# MOSFETS.net
KiCad netlist of a schematic drawn in Altium Designer
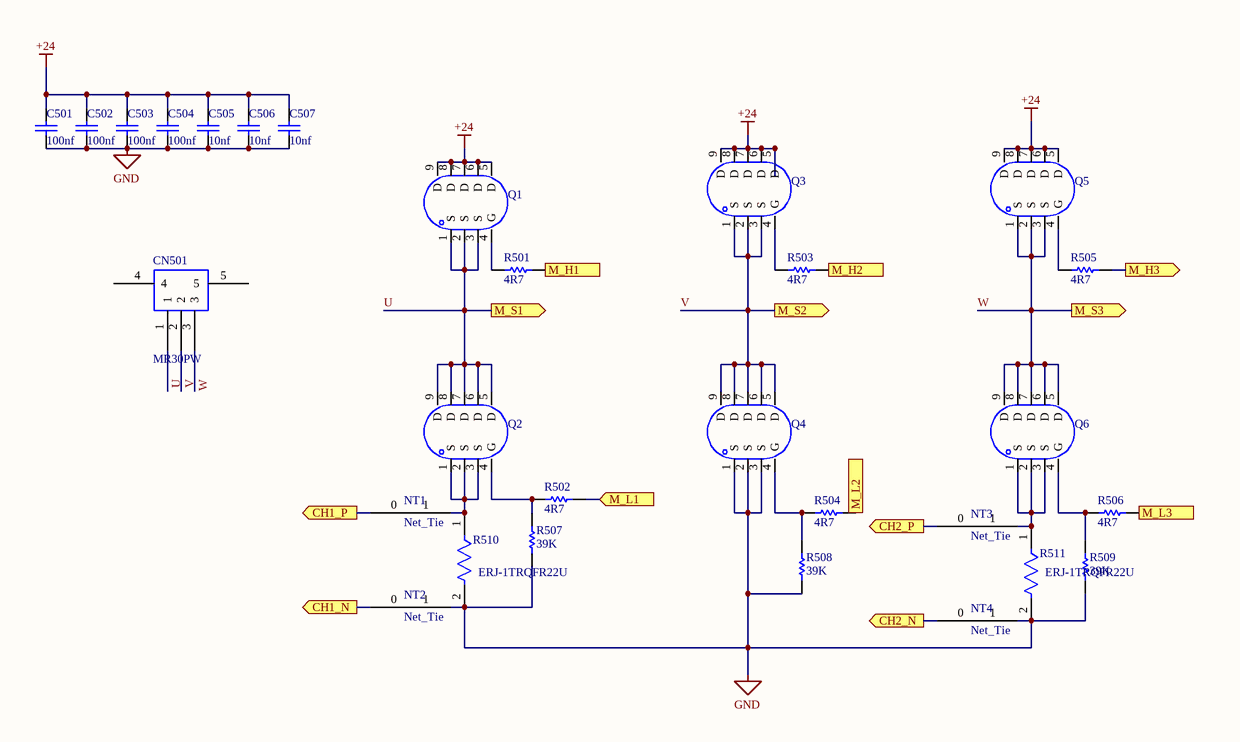
[diagram p0: MOSFETS.SchDoc]

(export (version "E")
  (design (tool "Eeschema 10.0.6"))
  (components
    (comp (ref "C501")
      (value "100nf")
      (footprint "AVX-1206-2_L")
      (description "Chip Capacitor, 1 nF, +/- 10%, -55 to 125 degC, 1206 (3216 Metric), RoHS, Tape and Reel")
      (fields (field (name "TOLERANCE") "10%") (field (name "PARTNUMBER") "1206GC102KAT1A"))
      (libsource (lib "Altium Content Vault") (part "CAP-NP-2"))
    )
    (comp (ref "C502")
      (value "100nf")
      (footprint "AVX-1206-2_L")
      (description "Chip Capacitor, 1 nF, +/- 10%, -55 to 125 degC, 1206 (3216 Metric), RoHS, Tape and Reel")
      (fields (field (name "TOLERANCE") "10%") (field (name "PARTNUMBER") "1206GC102KAT1A"))
      (libsource (lib "Altium Content Vault") (part "CAP-NP-2"))
    )
    (comp (ref "C503")
      (value "100nf")
      (footprint "AVX-1206-2_L")
      (description "Chip Capacitor, 1 nF, +/- 10%, -55 to 125 degC, 1206 (3216 Metric), RoHS, Tape and Reel")
      (fields (field (name "TOLERANCE") "10%") (field (name "PARTNUMBER") "1206GC102KAT1A"))
      (libsource (lib "Altium Content Vault") (part "CAP-NP-2"))
    )
    (comp (ref "C504")
      (value "100nf")
      (footprint "AVX-1206-2_L")
      (description "Chip Capacitor, 1 nF, +/- 10%, -55 to 125 degC, 1206 (3216 Metric), RoHS, Tape and Reel")
      (fields (field (name "TOLERANCE") "10%") (field (name "PARTNUMBER") "1206GC102KAT1A"))
      (libsource (lib "Altium Content Vault") (part "CAP-NP-2"))
    )
    (comp (ref "C505")
      (value "10nf")
      (footprint "AVX-1206-2_L")
      (description "Chip Capacitor, 1 nF, +/- 10%, -55 to 125 degC, 1206 (3216 Metric), RoHS, Tape and Reel")
      (fields (field (name "TOLERANCE") "10%") (field (name "PARTNUMBER") "1206GC102KAT1A"))
      (libsource (lib "Altium Content Vault") (part "CAP-NP-2"))
    )
    (comp (ref "C506")
      (value "10nf")
      (footprint "AVX-1206-2_L")
      (description "Chip Capacitor, 1 nF, +/- 10%, -55 to 125 degC, 1206 (3216 Metric), RoHS, Tape and Reel")
      (fields (field (name "TOLERANCE") "10%") (field (name "PARTNUMBER") "1206GC102KAT1A"))
      (libsource (lib "Altium Content Vault") (part "CAP-NP-2"))
    )
    (comp (ref "C507")
      (value "10nf")
      (footprint "AVX-1206-2_L")
      (description "Chip Capacitor, 1 nF, +/- 10%, -55 to 125 degC, 1206 (3216 Metric), RoHS, Tape and Reel")
      (fields (field (name "TOLERANCE") "10%") (field (name "PARTNUMBER") "1206GC102KAT1A"))
      (libsource (lib "Altium Content Vault") (part "CAP-NP-2"))
    )
    (comp (ref "CN501") (value "MR30PW") (footprint "MR30") (libsource (lib "MR30PW") (part "Component_1")))
    (comp (ref "NT1") (value "Net_Tie") (footprint "NT") (libsource (lib "NT") (part "Net_Tie")))
    (comp (ref "NT2") (value "Net_Tie") (footprint "NT") (libsource (lib "NT") (part "Net_Tie")))
    (comp (ref "NT3") (value "Net_Tie") (footprint "NT") (libsource (lib "NT") (part "Net_Tie")))
    (comp (ref "NT4") (value "Net_Tie") (footprint "NT") (libsource (lib "NT") (part "Net_Tie")))
    (comp (ref "Q1")
      (value "TPH1R403NL")
      (footprint "DSOP-8_L5.0-W5.0-P1.27-EP-TL")
      (fields (field (name "MANUFACTURER") "TOSHIBA(东芝)"))
      (libsource (lib "TPH1R403NL") (part "TPH1R403NL"))
    )
    (comp (ref "Q2")
      (value "TPH1R403NL")
      (footprint "DSOP-8_L5.0-W5.0-P1.27-EP-TL")
      (fields (field (name "MANUFACTURER") "TOSHIBA(东芝)"))
      (libsource (lib "TPH1R403NL") (part "TPH1R403NL"))
    )
    (comp (ref "Q3")
      (value "TPH1R403NL")
      (footprint "DSOP-8_L5.0-W5.0-P1.27-EP-TL")
      (fields (field (name "MANUFACTURER") "TOSHIBA(东芝)"))
      (libsource (lib "TPH1R403NL") (part "TPH1R403NL"))
    )
    (comp (ref "Q4")
      (value "TPH1R403NL")
      (footprint "DSOP-8_L5.0-W5.0-P1.27-EP-TL")
      (fields (field (name "MANUFACTURER") "TOSHIBA(东芝)"))
      (libsource (lib "TPH1R403NL") (part "TPH1R403NL"))
    )
    (comp (ref "Q5")
      (value "TPH1R403NL")
      (footprint "DSOP-8_L5.0-W5.0-P1.27-EP-TL")
      (fields (field (name "MANUFACTURER") "TOSHIBA(东芝)"))
      (libsource (lib "TPH1R403NL") (part "TPH1R403NL"))
    )
    (comp (ref "Q6")
      (value "TPH1R403NL")
      (footprint "DSOP-8_L5.0-W5.0-P1.27-EP-TL")
      (fields (field (name "MANUFACTURER") "TOSHIBA(东芝)"))
      (libsource (lib "TPH1R403NL") (part "TPH1R403NL"))
    )
    (comp (ref "R501")
      (value "4R7")
      (footprint "RESC1608X55X25ML10T15")
      (description "Chip Resistor, 0 Ohm, +/- 5%, 0.1 W, -55 to 155 degC, 0603 (1608 Metric), RoHS, Tape and Reel")
      (fields (field (name "TOLERANCE") "5%") (field (name "MANUFACTURER") "Yageo"))
      (libsource (lib "Altium Content Vault") (part "RES-2"))
    )
    (comp (ref "R502")
      (value "4R7")
      (footprint "RESC1608X55X25ML10T15")
      (description "Chip Resistor, 0 Ohm, +/- 5%, 0.1 W, -55 to 155 degC, 0603 (1608 Metric), RoHS, Tape and Reel")
      (fields (field (name "TOLERANCE") "5%") (field (name "MANUFACTURER") "Yageo"))
      (libsource (lib "Altium Content Vault") (part "RES-2"))
    )
    (comp (ref "R503")
      (value "4R7")
      (footprint "RESC1608X55X25ML10T15")
      (description "Chip Resistor, 0 Ohm, +/- 5%, 0.1 W, -55 to 155 degC, 0603 (1608 Metric), RoHS, Tape and Reel")
      (fields (field (name "TOLERANCE") "5%") (field (name "MANUFACTURER") "Yageo"))
      (libsource (lib "Altium Content Vault") (part "RES-2"))
    )
    (comp (ref "R504")
      (value "4R7")
      (footprint "RESC1608X55X25ML10T15")
      (description "Chip Resistor, 0 Ohm, +/- 5%, 0.1 W, -55 to 155 degC, 0603 (1608 Metric), RoHS, Tape and Reel")
      (fields (field (name "TOLERANCE") "5%") (field (name "MANUFACTURER") "Yageo"))
      (libsource (lib "Altium Content Vault") (part "RES-2"))
    )
    (comp (ref "R505")
      (value "4R7")
      (footprint "RESC1608X55X25ML10T15")
      (description "Chip Resistor, 0 Ohm, +/- 5%, 0.1 W, -55 to 155 degC, 0603 (1608 Metric), RoHS, Tape and Reel")
      (fields (field (name "TOLERANCE") "5%") (field (name "MANUFACTURER") "Yageo"))
      (libsource (lib "Altium Content Vault") (part "RES-2"))
    )
    (comp (ref "R506")
      (value "4R7")
      (footprint "RESC1608X55X25ML10T15")
      (description "Chip Resistor, 0 Ohm, +/- 5%, 0.1 W, -55 to 155 degC, 0603 (1608 Metric), RoHS, Tape and Reel")
      (fields (field (name "TOLERANCE") "5%") (field (name "MANUFACTURER") "Yageo"))
      (libsource (lib "Altium Content Vault") (part "RES-2"))
    )
    (comp (ref "R507")
      (value "39K")
      (footprint "RESC1608X55X25ML10T15")
      (description "Chip Resistor, 0 Ohm, +/- 5%, 0.1 W, -55 to 155 degC, 0603 (1608 Metric), RoHS, Tape and Reel")
      (fields (field (name "TOLERANCE") "5%") (field (name "MANUFACTURER") "Yageo"))
      (libsource (lib "Altium Content Vault") (part "RES-2"))
    )
    (comp (ref "R508")
      (value "39K")
      (footprint "RESC1608X55X25ML10T15")
      (description "Chip Resistor, 0 Ohm, +/- 5%, 0.1 W, -55 to 155 degC, 0603 (1608 Metric), RoHS, Tape and Reel")
      (fields (field (name "TOLERANCE") "5%") (field (name "MANUFACTURER") "Yageo"))
      (libsource (lib "Altium Content Vault") (part "RES-2"))
    )
    (comp (ref "R509")
      (value "39K")
      (footprint "RESC1608X55X25ML10T15")
      (description "Chip Resistor, 0 Ohm, +/- 5%, 0.1 W, -55 to 155 degC, 0603 (1608 Metric), RoHS, Tape and Reel")
      (fields (field (name "TOLERANCE") "5%") (field (name "MANUFACTURER") "Yageo"))
      (libsource (lib "Altium Content Vault") (part "RES-2"))
    )
    (comp (ref "R510")
      (value "ERJ-1TRQFR22U")
      (footprint "FP-ERJ1TR-MFG")
      (description "RES 0.22 OHM 1% 1W 2512")
      (fields
        (field (name "TOLERANCE") "1%")
        (field (name "OCTOPART") "https://octopart.com/erj1trqfr22u-panasonic-10566390")
      )
      (libsource (lib "Altium Content Vault") (part "1029c3af85768c4190bb7ad29bc67b5"))
    )
    (comp (ref "R511")
      (value "ERJ-1TRQFR22U")
      (footprint "FP-ERJ1TR-MFG")
      (description "RES 0.22 OHM 1% 1W 2512")
      (fields
        (field (name "TOLERANCE") "1%")
        (field (name "OCTOPART") "https://octopart.com/erj1trqfr22u-panasonic-10566390")
      )
      (libsource (lib "Altium Content Vault") (part "1029c3af85768c4190bb7ad29bc67b5"))
    )
  )
  (nets
    (net (code "1") (name "+24") (class "Default")
      (node (ref "C501") (pin "2") (pinfunction "2_2") (pintype "passive"))
      (node (ref "C502") (pin "2") (pinfunction "2_2") (pintype "passive"))
      (node (ref "C503") (pin "2") (pinfunction "2_2") (pintype "passive"))
      (node (ref "C504") (pin "2") (pinfunction "2_2") (pintype "passive"))
      (node (ref "C505") (pin "2") (pinfunction "2_2") (pintype "passive"))
      (node (ref "C506") (pin "2") (pinfunction "2_2") (pintype "passive"))
      (node (ref "C507") (pin "2") (pinfunction "2_2") (pintype "passive"))
      (node (ref "Q1") (pin "5") (pinfunction "D_5") (pintype "passive"))
      (node (ref "Q1") (pin "6") (pinfunction "D_6") (pintype "passive"))
      (node (ref "Q1") (pin "7") (pinfunction "D_7") (pintype "passive"))
      (node (ref "Q1") (pin "8") (pinfunction "D_8") (pintype "passive"))
      (node (ref "Q1") (pin "9") (pinfunction "D_9") (pintype "passive"))
      (node (ref "Q3") (pin "5") (pinfunction "D_5") (pintype "passive"))
      (node (ref "Q3") (pin "6") (pinfunction "D_6") (pintype "passive"))
      (node (ref "Q3") (pin "7") (pinfunction "D_7") (pintype "passive"))
      (node (ref "Q3") (pin "8") (pinfunction "D_8") (pintype "passive"))
      (node (ref "Q3") (pin "9") (pinfunction "D_9") (pintype "passive"))
      (node (ref "Q5") (pin "5") (pinfunction "D_5") (pintype "passive"))
      (node (ref "Q5") (pin "6") (pinfunction "D_6") (pintype "passive"))
      (node (ref "Q5") (pin "7") (pinfunction "D_7") (pintype "passive"))
      (node (ref "Q5") (pin "8") (pinfunction "D_8") (pintype "passive"))
      (node (ref "Q5") (pin "9") (pinfunction "D_9") (pintype "passive"))
    )
    (net (code "2") (name "/CH1_N") (class "Default") (node (ref "NT2") (pin "0") (pintype "passive")))
    (net (code "3") (name "/CH1_P") (class "Default") (node (ref "NT1") (pin "0") (pintype "passive")))
    (net (code "4") (name "/CH2_N") (class "Default") (node (ref "NT4") (pin "0") (pintype "passive")))
    (net (code "5") (name "/CH2_P") (class "Default") (node (ref "NT3") (pin "0") (pintype "passive")))
    (net (code "6") (name "/M_H1") (class "Default")
      (node (ref "R501") (pin "1") (pinfunction "1_1") (pintype "passive"))
    )
    (net (code "7") (name "/M_H2") (class "Default")
      (node (ref "R503") (pin "1") (pinfunction "1_1") (pintype "passive"))
    )
    (net (code "8") (name "/M_H3") (class "Default")
      (node (ref "R505") (pin "1") (pinfunction "1_1") (pintype "passive"))
    )
    (net (code "9") (name "/M_L1") (class "Default")
      (node (ref "R502") (pin "1") (pinfunction "1_1") (pintype "passive"))
    )
    (net (code "10") (name "/M_L2") (class "Default")
      (node (ref "R504") (pin "1") (pinfunction "1_1") (pintype "passive"))
    )
    (net (code "11") (name "/M_L3") (class "Default")
      (node (ref "R506") (pin "1") (pinfunction "1_1") (pintype "passive"))
    )
    (net (code "12") (name "/U") (class "Default")
      (node (ref "CN501") (pin "1") (pinfunction "1_1") (pintype "passive"))
      (node (ref "Q1") (pin "1") (pinfunction "S_1") (pintype "passive"))
      (node (ref "Q1") (pin "2") (pinfunction "S_2") (pintype "passive"))
      (node (ref "Q1") (pin "3") (pinfunction "S_3") (pintype "passive"))
      (node (ref "Q2") (pin "5") (pinfunction "D_5") (pintype "passive"))
      (node (ref "Q2") (pin "6") (pinfunction "D_6") (pintype "passive"))
      (node (ref "Q2") (pin "7") (pinfunction "D_7") (pintype "passive"))
      (node (ref "Q2") (pin "8") (pinfunction "D_8") (pintype "passive"))
      (node (ref "Q2") (pin "9") (pinfunction "D_9") (pintype "passive"))
    )
    (net (code "13") (name "/V") (class "Default")
      (node (ref "CN501") (pin "2") (pinfunction "2_2") (pintype "passive"))
      (node (ref "Q3") (pin "1") (pinfunction "S_1") (pintype "passive"))
      (node (ref "Q3") (pin "2") (pinfunction "S_2") (pintype "passive"))
      (node (ref "Q3") (pin "3") (pinfunction "S_3") (pintype "passive"))
      (node (ref "Q4") (pin "5") (pinfunction "D_5") (pintype "passive"))
      (node (ref "Q4") (pin "6") (pinfunction "D_6") (pintype "passive"))
      (node (ref "Q4") (pin "7") (pinfunction "D_7") (pintype "passive"))
      (node (ref "Q4") (pin "8") (pinfunction "D_8") (pintype "passive"))
      (node (ref "Q4") (pin "9") (pinfunction "D_9") (pintype "passive"))
    )
    (net (code "14") (name "/W") (class "Default")
      (node (ref "CN501") (pin "3") (pinfunction "3_3") (pintype "passive"))
      (node (ref "Q5") (pin "1") (pinfunction "S_1") (pintype "passive"))
      (node (ref "Q5") (pin "2") (pinfunction "S_2") (pintype "passive"))
      (node (ref "Q5") (pin "3") (pinfunction "S_3") (pintype "passive"))
      (node (ref "Q6") (pin "5") (pinfunction "D_5") (pintype "passive"))
      (node (ref "Q6") (pin "6") (pinfunction "D_6") (pintype "passive"))
      (node (ref "Q6") (pin "7") (pinfunction "D_7") (pintype "passive"))
      (node (ref "Q6") (pin "8") (pinfunction "D_8") (pintype "passive"))
      (node (ref "Q6") (pin "9") (pinfunction "D_9") (pintype "passive"))
    )
    (net (code "15") (name "GND") (class "Default")
      (node (ref "C501") (pin "1") (pinfunction "1_1") (pintype "passive"))
      (node (ref "C502") (pin "1") (pinfunction "1_1") (pintype "passive"))
      (node (ref "C503") (pin "1") (pinfunction "1_1") (pintype "passive"))
      (node (ref "C504") (pin "1") (pinfunction "1_1") (pintype "passive"))
      (node (ref "C505") (pin "1") (pinfunction "1_1") (pintype "passive"))
      (node (ref "C506") (pin "1") (pinfunction "1_1") (pintype "passive"))
      (node (ref "C507") (pin "1") (pinfunction "1_1") (pintype "passive"))
      (node (ref "NT2") (pin "1") (pintype "passive"))
      (node (ref "NT4") (pin "1") (pintype "passive"))
      (node (ref "Q4") (pin "1") (pinfunction "S_1") (pintype "passive"))
      (node (ref "Q4") (pin "2") (pinfunction "S_2") (pintype "passive"))
      (node (ref "Q4") (pin "3") (pinfunction "S_3") (pintype "passive"))
      (node (ref "R507") (pin "1") (pinfunction "1_1") (pintype "passive"))
      (node (ref "R508") (pin "1") (pinfunction "1_1") (pintype "passive"))
      (node (ref "R509") (pin "1") (pinfunction "1_1") (pintype "passive"))
      (node (ref "R510") (pin "2") (pinfunction "2_2") (pintype "passive"))
      (node (ref "R511") (pin "2") (pinfunction "2_2") (pintype "passive"))
    )
    (net (code "16") (name "Net-(NT1-Pad1)") (class "Default")
      (node (ref "NT1") (pin "1") (pintype "passive"))
      (node (ref "Q2") (pin "1") (pinfunction "S_1") (pintype "passive"))
      (node (ref "Q2") (pin "2") (pinfunction "S_2") (pintype "passive"))
      (node (ref "Q2") (pin "3") (pinfunction "S_3") (pintype "passive"))
      (node (ref "R510") (pin "1") (pinfunction "1_1") (pintype "passive"))
    )
    (net (code "17") (name "Net-(NT3-Pad1)") (class "Default")
      (node (ref "NT3") (pin "1") (pintype "passive"))
      (node (ref "Q6") (pin "1") (pinfunction "S_1") (pintype "passive"))
      (node (ref "Q6") (pin "2") (pinfunction "S_2") (pintype "passive"))
      (node (ref "Q6") (pin "3") (pinfunction "S_3") (pintype "passive"))
      (node (ref "R511") (pin "1") (pinfunction "1_1") (pintype "passive"))
    )
    (net (code "18") (name "Net-(Q1-G)") (class "Default")
      (node (ref "Q1") (pin "4") (pinfunction "G_4") (pintype "passive"))
      (node (ref "R501") (pin "2") (pinfunction "2_2") (pintype "passive"))
    )
    (net (code "19") (name "Net-(Q2-G)") (class "Default")
      (node (ref "Q2") (pin "4") (pinfunction "G_4") (pintype "passive"))
      (node (ref "R502") (pin "2") (pinfunction "2_2") (pintype "passive"))
      (node (ref "R507") (pin "2") (pinfunction "2_2") (pintype "passive"))
    )
    (net (code "20") (name "Net-(Q3-G)") (class "Default")
      (node (ref "Q3") (pin "4") (pinfunction "G_4") (pintype "passive"))
      (node (ref "R503") (pin "2") (pinfunction "2_2") (pintype "passive"))
    )
    (net (code "21") (name "Net-(Q4-G)") (class "Default")
      (node (ref "Q4") (pin "4") (pinfunction "G_4") (pintype "passive"))
      (node (ref "R504") (pin "2") (pinfunction "2_2") (pintype "passive"))
      (node (ref "R508") (pin "2") (pinfunction "2_2") (pintype "passive"))
    )
    (net (code "22") (name "Net-(Q5-G)") (class "Default")
      (node (ref "Q5") (pin "4") (pinfunction "G_4") (pintype "passive"))
      (node (ref "R505") (pin "2") (pinfunction "2_2") (pintype "passive"))
    )
    (net (code "23") (name "Net-(Q6-G)") (class "Default")
      (node (ref "Q6") (pin "4") (pinfunction "G_4") (pintype "passive"))
      (node (ref "R506") (pin "2") (pinfunction "2_2") (pintype "passive"))
      (node (ref "R509") (pin "2") (pinfunction "2_2") (pintype "passive"))
    )
    (net (code "24") (name "unconnected-(CN501-Pad4)") (class "Default")
      (node (ref "CN501") (pin "4") (pinfunction "4_4") (pintype "passive"))
    )
    (net (code "25") (name "unconnected-(CN501-Pad5)") (class "Default")
      (node (ref "CN501") (pin "5") (pinfunction "5_5") (pintype "passive"))
    )
  )
)
